# rfrNewMemberProject.net
KiCad netlist of a schematic drawn in Altium Designer
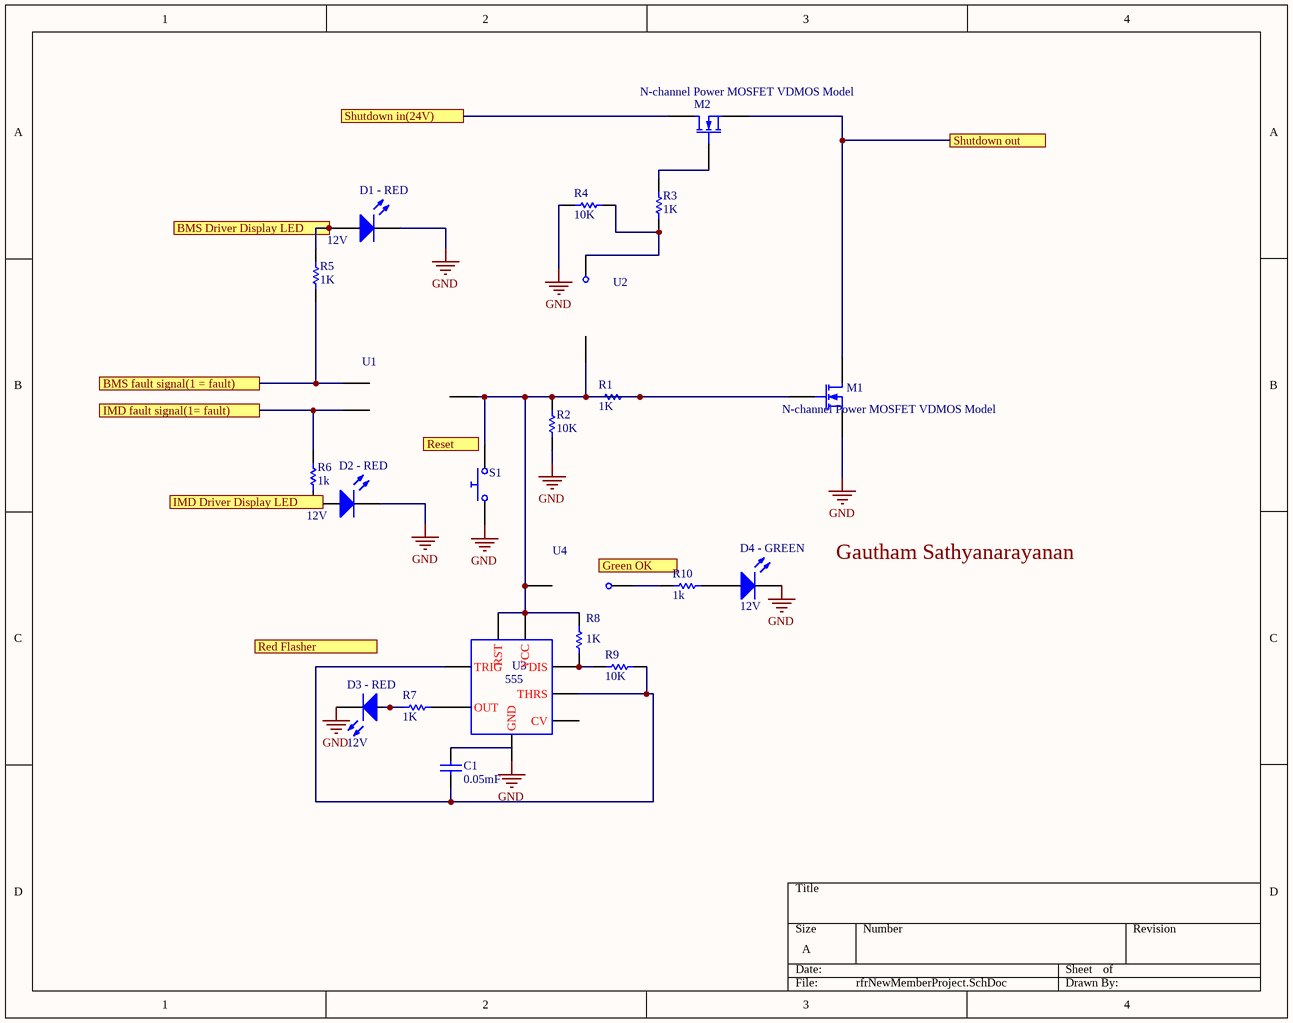
[diagram p0: rfrNewMemberProject.SchDoc]

(export (version "E")
  (design (tool "Eeschema 10.0.6"))
  (components
    (comp (ref "C1")
      (value "0.05mF")
      (description "Capacitor")
      (libsource (lib "Simulation Generic Components") (part "Capacitor"))
    )
    (comp (ref "D1 - RED")
      (value "12V")
      (description "Light-Emitting Diode")
      (libsource (lib "Simulation Generic Components") (part "LED"))
    )
    (comp (ref "D2 - RED")
      (value "12V")
      (description "Light-Emitting Diode")
      (libsource (lib "Simulation Generic Components") (part "LED"))
    )
    (comp (ref "D3 - RED")
      (value "12V")
      (description "Light-Emitting Diode")
      (libsource (lib "Simulation Generic Components") (part "LED"))
    )
    (comp (ref "D4 - GREEN")
      (value "12V")
      (description "Light-Emitting Diode")
      (libsource (lib "Simulation Generic Components") (part "LED"))
    )
    (comp (ref "M1")
      (value "N-channel Power MOSFET VDMOS Model")
      (libsource (lib "Simulation Generic Components") (part "MOSFET N-ch VDMOS"))
    )
    (comp (ref "M2")
      (value "N-channel Power MOSFET VDMOS Model")
      (libsource (lib "Simulation Generic Components") (part "MOSFET N-ch VDMOS"))
    )
    (comp (ref "R1")
      (value "1K")
      (description "Resistor")
      (libsource (lib "Simulation Generic Components") (part "Resistor"))
    )
    (comp (ref "R2")
      (value "10K")
      (description "Resistor")
      (libsource (lib "Simulation Generic Components") (part "Resistor"))
    )
    (comp (ref "R3")
      (value "1K")
      (description "Resistor")
      (libsource (lib "Simulation Generic Components") (part "Resistor"))
    )
    (comp (ref "R4")
      (value "10K")
      (description "Resistor")
      (libsource (lib "Simulation Generic Components") (part "Resistor"))
    )
    (comp (ref "R5")
      (value "1K")
      (description "Resistor")
      (libsource (lib "Simulation Generic Components") (part "Resistor"))
    )
    (comp (ref "R6")
      (value "1k")
      (description "Resistor")
      (libsource (lib "Simulation Generic Components") (part "Resistor"))
    )
    (comp (ref "R7")
      (value "1K")
      (description "Resistor")
      (libsource (lib "Simulation Generic Components") (part "Resistor"))
    )
    (comp (ref "R8")
      (value "1K")
      (description "Resistor")
      (libsource (lib "Simulation Generic Components") (part "Resistor"))
    )
    (comp (ref "R9")
      (value "10K")
      (description "Resistor")
      (libsource (lib "Simulation Generic Components") (part "Resistor"))
    )
    (comp (ref "R10")
      (value "1k")
      (description "Resistor")
      (libsource (lib "Simulation Generic Components") (part "Resistor"))
    )
    (comp (ref "S1")
      (value "Push Button Normally Opened")
      (libsource (lib "Simulation Generic Components") (part "Push Button NO"))
    )
    (comp (ref "U1")
      (value "Digital OR Gate")
      (libsource (lib "Simulation Generic Components") (part "Digital OR"))
    )
    (comp (ref "U2")
      (value "Digital NOT Gate")
      (libsource (lib "Simulation Generic Components") (part "Digital NOT"))
    )
    (comp (ref "U3")
      (value "555")
      (description "Timer 555")
      (libsource (lib "Simulation Generic Components") (part "555"))
    )
    (comp (ref "U4")
      (value "Digital NOT Gate")
      (libsource (lib "Simulation Generic Components") (part "Digital NOT"))
    )
  )
  (nets
    (net (code "1") (name "/BMS Driver Display LED") (class "Default")
      (node (ref "D1 - RED") (pin "1") (pinfunction "A_1") (pintype "passive"))
      (node (ref "R5") (pin "2") (pinfunction "2_2") (pintype "passive"))
    )
    (net (code "2") (name "/BMS fault signal(1 = fault)") (class "Default")
      (node (ref "R5") (pin "1") (pinfunction "1_1") (pintype "passive"))
      (node (ref "U1") (pin "1") (pinfunction "1_1") (pintype "passive"))
    )
    (net (code "6") (name "/IMD fault signal(1= fault)") (class "Default")
      (node (ref "R6") (pin "2") (pinfunction "2_2") (pintype "passive"))
      (node (ref "U1") (pin "2") (pinfunction "2_2") (pintype "passive"))
    )
    (net (code "9") (name "/Shutdown in(24V)") (class "Default")
      (node (ref "M2") (pin "1") (pinfunction "D_1") (pintype "passive"))
    )
    (net (code "10") (name "/Shutdown out") (class "Default")
      (node (ref "M1") (pin "1") (pinfunction "D_1") (pintype "passive"))
      (node (ref "M2") (pin "3") (pinfunction "S_3") (pintype "passive"))
    )
    (net (code "11") (name "GND") (class "Default")
      (node (ref "D1 - RED") (pin "2") (pinfunction "K_2") (pintype "passive"))
      (node (ref "D2 - RED") (pin "2") (pinfunction "K_2") (pintype "passive"))
      (node (ref "D3 - RED") (pin "2") (pinfunction "K_2") (pintype "passive"))
      (node (ref "D4 - GREEN") (pin "2") (pinfunction "K_2") (pintype "passive"))
      (node (ref "M1") (pin "3") (pinfunction "S_3") (pintype "passive"))
      (node (ref "R2") (pin "1") (pinfunction "1_1") (pintype "passive"))
      (node (ref "R4") (pin "1") (pinfunction "1_1") (pintype "passive"))
      (node (ref "S1") (pin "1") (pinfunction "1_1") (pintype "passive"))
      (node (ref "U3") (pin "1") (pinfunction "GND_1") (pintype "passive"))
    )
    (net (code "12") (name "Net-(D2 - RED-A)") (class "Default")
      (node (ref "D2 - RED") (pin "1") (pinfunction "A_1") (pintype "passive"))
      (node (ref "R6") (pin "1") (pinfunction "1_1") (pintype "passive"))
    )
    (net (code "13") (name "Net-(D3 - RED-A)") (class "Default")
      (node (ref "D3 - RED") (pin "1") (pinfunction "A_1") (pintype "passive"))
      (node (ref "R7") (pin "1") (pinfunction "1_1") (pintype "passive"))
    )
    (net (code "14") (name "Net-(D4 - GREEN-A)") (class "Default")
      (node (ref "D4 - GREEN") (pin "1") (pinfunction "A_1") (pintype "passive"))
      (node (ref "R10") (pin "2") (pinfunction "2_2") (pintype "passive"))
    )
    (net (code "15") (name "Net-(M1-G)") (class "Default")
      (node (ref "M1") (pin "2") (pinfunction "G_2") (pintype "passive"))
      (node (ref "R1") (pin "1") (pinfunction "1_1") (pintype "passive"))
      (node (ref "R1") (pin "2") (pinfunction "2_2") (pintype "passive"))
      (node (ref "R2") (pin "2") (pinfunction "2_2") (pintype "passive"))
      (node (ref "R8") (pin "2") (pinfunction "2_2") (pintype "passive"))
      (node (ref "S1") (pin "2") (pinfunction "2_2") (pintype "passive"))
      (node (ref "U1") (pin "3") (pinfunction "3_3") (pintype "passive"))
      (node (ref "U2") (pin "1") (pinfunction "1_1") (pintype "passive"))
      (node (ref "U3") (pin "4") (pinfunction "RST_4") (pintype "passive"))
      (node (ref "U3") (pin "8") (pinfunction "VCC_8") (pintype "passive"))
      (node (ref "U4") (pin "1") (pinfunction "1_1") (pintype "passive"))
    )
    (net (code "16") (name "Net-(M2-G)") (class "Default")
      (node (ref "M2") (pin "2") (pinfunction "G_2") (pintype "passive"))
      (node (ref "R3") (pin "2") (pinfunction "2_2") (pintype "passive"))
    )
    (net (code "17") (name "Net-(R3-Pad1)") (class "Default")
      (node (ref "R3") (pin "1") (pinfunction "1_1") (pintype "passive"))
      (node (ref "R4") (pin "2") (pinfunction "2_2") (pintype "passive"))
      (node (ref "U2") (pin "2") (pinfunction "2_2") (pintype "passive"))
    )
    (net (code "18") (name "Net-(R10-Pad1)") (class "Default")
      (node (ref "R10") (pin "1") (pinfunction "1_1") (pintype "passive"))
      (node (ref "U4") (pin "2") (pinfunction "2_2") (pintype "passive"))
    )
    (net (code "19") (name "Net-(U3-DIS)") (class "Default")
      (node (ref "R8") (pin "1") (pinfunction "1_1") (pintype "passive"))
      (node (ref "R9") (pin "1") (pinfunction "1_1") (pintype "passive"))
      (node (ref "U3") (pin "7") (pinfunction "DIS_7") (pintype "passive"))
    )
    (net (code "20") (name "Net-(U3-OUT)") (class "Default")
      (node (ref "R7") (pin "2") (pinfunction "2_2") (pintype "passive"))
      (node (ref "U3") (pin "3") (pinfunction "OUT_3") (pintype "passive"))
    )
    (net (code "21") (name "Net-(U3-THRS)") (class "Default")
      (node (ref "C1") (pin "1") (pinfunction "1_1") (pintype "passive"))
      (node (ref "R9") (pin "2") (pinfunction "2_2") (pintype "passive"))
      (node (ref "U3") (pin "2") (pinfunction "TRIG_2") (pintype "passive"))
      (node (ref "U3") (pin "6") (pinfunction "THRS_6") (pintype "passive"))
    )
    (net (code "22") (name "unconnected-(C1-Pad2)") (class "Default")
      (node (ref "C1") (pin "2") (pinfunction "2_2") (pintype "passive"))
    )
    (net (code "23") (name "unconnected-(U3-CV-Pad5)") (class "Default")
      (node (ref "U3") (pin "5") (pinfunction "CV_5") (pintype "passive"))
    )
  )
)
